# Striptease-Teensy4_1.net
KiCad netlist of a schematic drawn in EAGLE
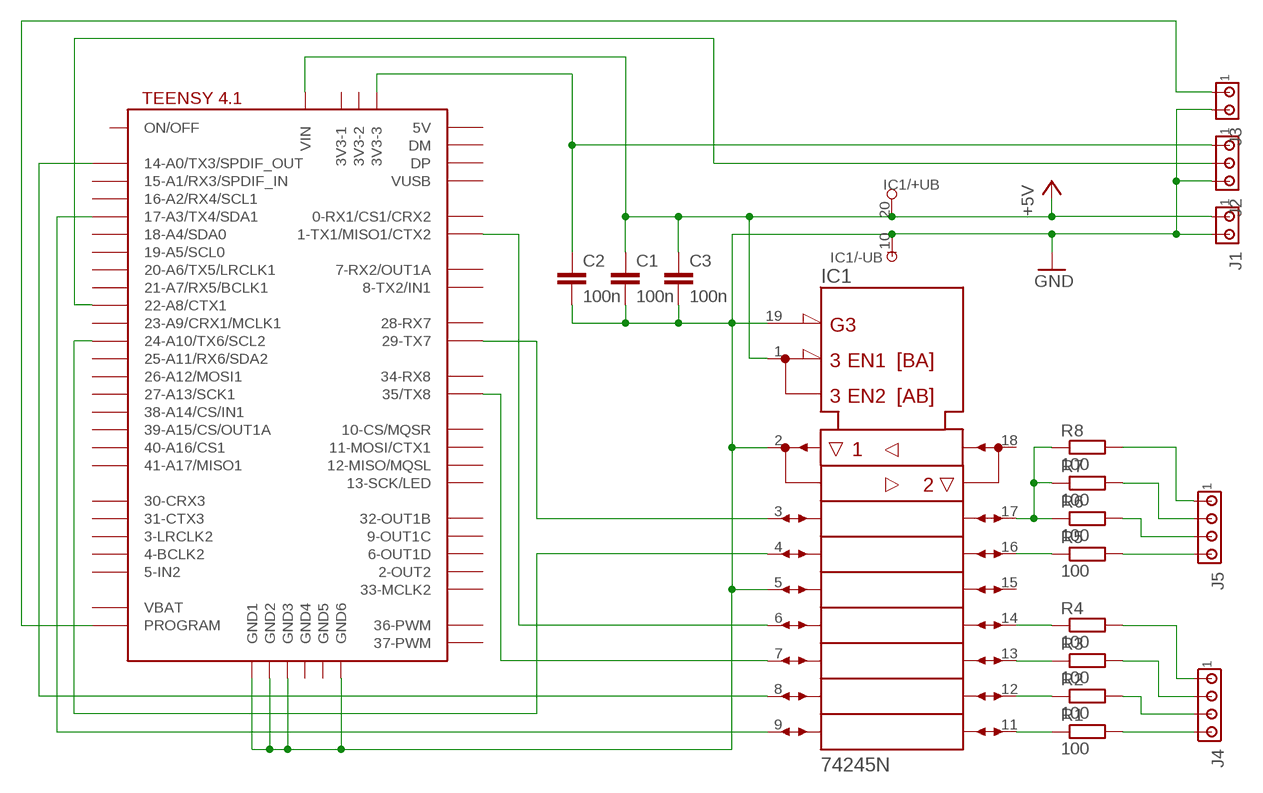
[diagram p0: schematic, sheet 1]

(export (version "E")
  (design (tool "Eeschema 10.0.6"))
  (components
    (comp (ref "C1")
      (value "100n")
      (footprint "eagle-import:C050-025X075")
      (libsource (lib "eagle-import") (part "C-EU050-025X075"))
    )
    (comp (ref "C2")
      (value "100n")
      (footprint "eagle-import:C050-025X075")
      (libsource (lib "eagle-import") (part "C-EU050-025X075"))
    )
    (comp (ref "C3")
      (value "100n")
      (footprint "eagle-import:C050-025X075")
      (libsource (lib "eagle-import") (part "C-EU050-025X075"))
    )
    (comp (ref "IC1")
      (value "74245N")
      (footprint "eagle-import:DIL20")
      (libsource (lib "eagle-import") (part "74245N"))
    )
    (comp (ref "J1")
      (value "MTA02-100")
      (footprint "eagle-import:10X02MTA")
      (libsource (lib "eagle-import") (part "MTA02-100"))
    )
    (comp (ref "J2")
      (value "MTA03-100")
      (footprint "eagle-import:10X03MTA")
      (libsource (lib "eagle-import") (part "MTA03-100"))
    )
    (comp (ref "J3")
      (value "MTA02-100")
      (footprint "eagle-import:10X02MTA")
      (libsource (lib "eagle-import") (part "MTA02-100"))
    )
    (comp (ref "J4")
      (value "MTA04-100")
      (footprint "eagle-import:10X04MTA")
      (libsource (lib "eagle-import") (part "MTA04-100"))
    )
    (comp (ref "J5")
      (value "MTA04-100")
      (footprint "eagle-import:10X04MTA")
      (libsource (lib "eagle-import") (part "MTA04-100"))
    )
    (comp (ref "R1")
      (value "100")
      (footprint "eagle-import:0207_10")
      (libsource (lib "eagle-import") (part "R-EU_0207/10"))
    )
    (comp (ref "R2")
      (value "100")
      (footprint "eagle-import:0207_10")
      (libsource (lib "eagle-import") (part "R-EU_0207/10"))
    )
    (comp (ref "R3")
      (value "100")
      (footprint "eagle-import:0207_10")
      (libsource (lib "eagle-import") (part "R-EU_0207/10"))
    )
    (comp (ref "R4")
      (value "100")
      (footprint "eagle-import:0207_10")
      (libsource (lib "eagle-import") (part "R-EU_0207/10"))
    )
    (comp (ref "R5")
      (value "100")
      (footprint "eagle-import:0207_10")
      (libsource (lib "eagle-import") (part "R-EU_0207/10"))
    )
    (comp (ref "R6")
      (value "100")
      (footprint "eagle-import:0207_10")
      (libsource (lib "eagle-import") (part "R-EU_0207/10"))
    )
    (comp (ref "R7")
      (value "100")
      (footprint "eagle-import:0207_10")
      (libsource (lib "eagle-import") (part "R-EU_0207/10"))
    )
    (comp (ref "R8")
      (value "100")
      (footprint "eagle-import:0207_10")
      (libsource (lib "eagle-import") (part "R-EU_0207/10"))
    )
    (comp (ref "U$3")
      (value "TEENSY41-E")
      (footprint "eagle-import:TENNSY41-E")
      (libsource (lib "eagle-import") (part "TEENSY41-E"))
    )
  )
  (nets
    (net (code "1") (name "+5V") (class "Default")
      (node (ref "C1") (pin "1") (pinfunction "1_1") (pintype "passive"))
      (node (ref "C3") (pin "1") (pinfunction "1_1") (pintype "passive"))
      (node (ref "IC1") (pin "1") (pinfunction "DIR_1") (pintype "input"))
      (node (ref "IC1") (pin "20") (pinfunction "+UB_20") (pintype "power_in"))
      (node (ref "J1") (pin "1") (pinfunction "1_1") (pintype "passive"))
      (node (ref "U$3") (pin "VIN") (pinfunction "VIN_VIN") (pintype "bidirectional"))
    )
    (net (code "2") (name "GND") (class "Default")
      (node (ref "C1") (pin "2") (pinfunction "2_2") (pintype "passive"))
      (node (ref "C2") (pin "2") (pinfunction "2_2") (pintype "passive"))
      (node (ref "C3") (pin "2") (pinfunction "2_2") (pintype "passive"))
      (node (ref "IC1") (pin "10") (pinfunction "-UB_10") (pintype "power_in"))
      (node (ref "IC1") (pin "19") (pinfunction "~{G}_19") (pintype "input"))
      (node (ref "IC1") (pin "2") (pinfunction "A1_2") (pintype "bidirectional"))
      (node (ref "IC1") (pin "5") (pinfunction "A4_5") (pintype "bidirectional"))
      (node (ref "J1") (pin "2") (pinfunction "2_2") (pintype "passive"))
      (node (ref "J2") (pin "3") (pinfunction "3_3") (pintype "passive"))
      (node (ref "J3") (pin "2") (pinfunction "2_2") (pintype "passive"))
      (node (ref "U$3") (pin "GND1") (pinfunction "GND1_GND1") (pintype "bidirectional"))
      (node (ref "U$3") (pin "GND2") (pinfunction "GND2_GND2") (pintype "bidirectional"))
      (node (ref "U$3") (pin "GND3") (pinfunction "GND3_GND3") (pintype "bidirectional"))
      (node (ref "U$3") (pin "GND6") (pinfunction "GND6_GND6") (pintype "bidirectional"))
    )
    (net (code "3") (name "Net-(C2-Pad1)") (class "Default")
      (node (ref "C2") (pin "1") (pinfunction "1_1") (pintype "passive"))
      (node (ref "J2") (pin "1") (pinfunction "1_1") (pintype "passive"))
      (node (ref "U$3") (pin "3V3-3") (pinfunction "3V3-3_3V3-3") (pintype "bidirectional"))
    )
    (net (code "4") (name "Net-(IC1C-A2)") (class "Default")
      (node (ref "IC1") (pin "3") (pinfunction "A2_3") (pintype "bidirectional"))
      (node (ref "U$3") (pin "29-TX7") (pinfunction "29-TX7_29-TX7") (pintype "bidirectional"))
    )
    (net (code "5") (name "Net-(IC1C-A3)") (class "Default")
      (node (ref "IC1") (pin "4") (pinfunction "A3_4") (pintype "bidirectional"))
      (node (ref "U$3") (pin "24-A10/TX6/SCL2") (pinfunction "24-A10/TX6/SCL2_24-A10/TX6/SCL2") (pintype "bidirectional"))
    )
    (net (code "6") (name "Net-(IC1C-A5)") (class "Default")
      (node (ref "IC1") (pin "6") (pinfunction "A5_6") (pintype "bidirectional"))
      (node (ref "U$3") (pin "1-TX1/MISO1/CTX2") (pinfunction "1-TX1/MISO1/CTX2_1-TX1/MISO1/CTX2") (pintype "bidirectional"))
    )
    (net (code "7") (name "Net-(IC1C-A6)") (class "Default")
      (node (ref "IC1") (pin "7") (pinfunction "A6_7") (pintype "bidirectional"))
      (node (ref "U$3") (pin "35-TX8") (pinfunction "35/TX8_35-TX8") (pintype "bidirectional"))
    )
    (net (code "8") (name "Net-(IC1C-A7)") (class "Default")
      (node (ref "IC1") (pin "8") (pinfunction "A7_8") (pintype "bidirectional"))
      (node (ref "U$3") (pin "14-A0/TX3/SPDIF_OUT") (pinfunction "14-A0/TX3/SPDIF_OUT_14-A0/TX3/SPDIF_OUT") (pintype "bidirectional"))
    )
    (net (code "9") (name "Net-(IC1C-A8)") (class "Default")
      (node (ref "IC1") (pin "9") (pinfunction "A8_9") (pintype "bidirectional"))
      (node (ref "U$3") (pin "17-A3/TX4/SDA1") (pinfunction "17-A3/TX4/SDA1_17-A3/TX4/SDA1") (pintype "bidirectional"))
    )
    (net (code "10") (name "Net-(IC1C-B2)") (class "Default")
      (node (ref "IC1") (pin "17") (pinfunction "B2_17") (pintype "bidirectional"))
      (node (ref "R6") (pin "1") (pinfunction "1_1") (pintype "passive"))
      (node (ref "R7") (pin "1") (pinfunction "1_1") (pintype "passive"))
      (node (ref "R8") (pin "1") (pinfunction "1_1") (pintype "passive"))
    )
    (net (code "11") (name "Net-(IC1C-B3)") (class "Default")
      (node (ref "IC1") (pin "16") (pinfunction "B3_16") (pintype "bidirectional"))
      (node (ref "R5") (pin "1") (pinfunction "1_1") (pintype "passive"))
    )
    (net (code "12") (name "Net-(IC1C-B5)") (class "Default")
      (node (ref "IC1") (pin "14") (pinfunction "B5_14") (pintype "bidirectional"))
      (node (ref "R4") (pin "1") (pinfunction "1_1") (pintype "passive"))
    )
    (net (code "13") (name "Net-(IC1C-B6)") (class "Default")
      (node (ref "IC1") (pin "13") (pinfunction "B6_13") (pintype "bidirectional"))
      (node (ref "R3") (pin "1") (pinfunction "1_1") (pintype "passive"))
    )
    (net (code "14") (name "Net-(IC1C-B7)") (class "Default")
      (node (ref "IC1") (pin "12") (pinfunction "B7_12") (pintype "bidirectional"))
      (node (ref "R2") (pin "1") (pinfunction "1_1") (pintype "passive"))
    )
    (net (code "15") (name "Net-(IC1C-B8)") (class "Default")
      (node (ref "IC1") (pin "11") (pinfunction "B8_11") (pintype "bidirectional"))
      (node (ref "R1") (pin "1") (pinfunction "1_1") (pintype "passive"))
    )
    (net (code "16") (name "Net-(J2-Pad2)") (class "Default")
      (node (ref "J2") (pin "2") (pinfunction "2_2") (pintype "passive"))
      (node (ref "U$3") (pin "22-A8/CTX1") (pinfunction "22-A8/CTX1_22-A8/CTX1") (pintype "bidirectional"))
    )
    (net (code "17") (name "Net-(J3-Pad1)") (class "Default")
      (node (ref "J3") (pin "1") (pinfunction "1_1") (pintype "passive"))
      (node (ref "U$3") (pin "PROGRAM") (pinfunction "PROGRAM_PROGRAM") (pintype "bidirectional"))
    )
    (net (code "18") (name "Net-(J4-Pad1)") (class "Default")
      (node (ref "J4") (pin "1") (pinfunction "1_1") (pintype "passive"))
      (node (ref "R4") (pin "2") (pinfunction "2_2") (pintype "passive"))
    )
    (net (code "19") (name "Net-(J4-Pad2)") (class "Default")
      (node (ref "J4") (pin "2") (pinfunction "2_2") (pintype "passive"))
      (node (ref "R3") (pin "2") (pinfunction "2_2") (pintype "passive"))
    )
    (net (code "20") (name "Net-(J4-Pad3)") (class "Default")
      (node (ref "J4") (pin "3") (pinfunction "3_3") (pintype "passive"))
      (node (ref "R2") (pin "2") (pinfunction "2_2") (pintype "passive"))
    )
    (net (code "21") (name "Net-(J4-Pad4)") (class "Default")
      (node (ref "J4") (pin "4") (pinfunction "4_4") (pintype "passive"))
      (node (ref "R1") (pin "2") (pinfunction "2_2") (pintype "passive"))
    )
    (net (code "22") (name "Net-(J5-Pad1)") (class "Default")
      (node (ref "J5") (pin "1") (pinfunction "1_1") (pintype "passive"))
      (node (ref "R8") (pin "2") (pinfunction "2_2") (pintype "passive"))
    )
    (net (code "23") (name "Net-(J5-Pad2)") (class "Default")
      (node (ref "J5") (pin "2") (pinfunction "2_2") (pintype "passive"))
      (node (ref "R7") (pin "2") (pinfunction "2_2") (pintype "passive"))
    )
    (net (code "24") (name "Net-(J5-Pad3)") (class "Default")
      (node (ref "J5") (pin "3") (pinfunction "3_3") (pintype "passive"))
      (node (ref "R6") (pin "2") (pinfunction "2_2") (pintype "passive"))
    )
    (net (code "25") (name "Net-(J5-Pad4)") (class "Default")
      (node (ref "J5") (pin "4") (pinfunction "4_4") (pintype "passive"))
      (node (ref "R5") (pin "2") (pinfunction "2_2") (pintype "passive"))
    )
    (net (code "26") (name "unconnected-(IC1C-B1-Pad18)") (class "Default")
      (node (ref "IC1") (pin "18") (pinfunction "B1_18") (pintype "bidirectional"))
    )
    (net (code "27") (name "unconnected-(IC1C-B4-Pad15)") (class "Default")
      (node (ref "IC1") (pin "15") (pinfunction "B4_15") (pintype "bidirectional"))
    )
    (net (code "28") (name "unconnected-(U$3-5V-Pad+5V)") (class "Default")
      (node (ref "U$3") (pin "+5V") (pinfunction "5V_+5V") (pintype "bidirectional"))
    )
    (net (code "29") (name "unconnected-(U$3-10-CS{slash}MQSR-Pad10-CS\\MQSR)") (class "Default")
      (node (ref "U$3") (pin "10-CS\\MQSR") (pinfunction "10-CS/MQSR_10-CS\\MQSR") (pintype "bidirectional"))
    )
    (net (code "30") (name "unconnected-(U$3-Pad0-RX1{slash}CS1{slash}CRX2)") (class "Default")
      (node (ref "U$3") (pin "0-RX1/CS1/CRX2") (pinfunction "0-RX1/CS1/CRX2_0-RX1/CS1/CRX2") (pintype "bidirectional"))
    )
    (net (code "31") (name "unconnected-(U$3-Pad2-OUT2)") (class "Default")
      (node (ref "U$3") (pin "2-OUT2") (pinfunction "2-OUT2_2-OUT2") (pintype "bidirectional"))
    )
    (net (code "32") (name "unconnected-(U$3-Pad3-LRCLK2)") (class "Default")
      (node (ref "U$3") (pin "3-LRCLK2") (pinfunction "3-LRCLK2_3-LRCLK2") (pintype "bidirectional"))
    )
    (net (code "33") (name "unconnected-(U$3-Pad3V3-1)") (class "Default")
      (node (ref "U$3") (pin "3V3-1") (pinfunction "3V3-1_3V3-1") (pintype "bidirectional"))
    )
    (net (code "34") (name "unconnected-(U$3-Pad3V3-2)") (class "Default")
      (node (ref "U$3") (pin "3V3-2") (pinfunction "3V3-2_3V3-2") (pintype "bidirectional"))
    )
    (net (code "35") (name "unconnected-(U$3-Pad4-BCLK2)") (class "Default")
      (node (ref "U$3") (pin "4-BCLK2") (pinfunction "4-BCLK2_4-BCLK2") (pintype "bidirectional"))
    )
    (net (code "36") (name "unconnected-(U$3-Pad5-IN2)") (class "Default")
      (node (ref "U$3") (pin "5-IN2") (pinfunction "5-IN2_5-IN2") (pintype "bidirectional"))
    )
    (net (code "37") (name "unconnected-(U$3-Pad6-OUT1D)") (class "Default")
      (node (ref "U$3") (pin "6-OUT1D") (pinfunction "6-OUT1D_6-OUT1D") (pintype "bidirectional"))
    )
    (net (code "38") (name "unconnected-(U$3-Pad7-RX2{slash}OUT1A)") (class "Default")
      (node (ref "U$3") (pin "7-RX2/OUT1A") (pinfunction "7-RX2/OUT1A_7-RX2/OUT1A") (pintype "bidirectional"))
    )
    (net (code "39") (name "unconnected-(U$3-Pad8-TX2{slash}IN1)") (class "Default")
      (node (ref "U$3") (pin "8-TX2/IN1") (pinfunction "8-TX2/IN1_8-TX2/IN1") (pintype "bidirectional"))
    )
    (net (code "40") (name "unconnected-(U$3-Pad9-OUT1C)") (class "Default")
      (node (ref "U$3") (pin "9-OUT1C") (pinfunction "9-OUT1C_9-OUT1C") (pintype "bidirectional"))
    )
    (net (code "41") (name "unconnected-(U$3-Pad11-MOSI{slash}CTX1)") (class "Default")
      (node (ref "U$3") (pin "11-MOSI/CTX1") (pinfunction "11-MOSI/CTX1_11-MOSI/CTX1") (pintype "bidirectional"))
    )
    (net (code "42") (name "unconnected-(U$3-Pad12-MISO{slash}MQSL)") (class "Default")
      (node (ref "U$3") (pin "12-MISO/MQSL") (pinfunction "12-MISO/MQSL_12-MISO/MQSL") (pintype "bidirectional"))
    )
    (net (code "43") (name "unconnected-(U$3-Pad13-SCK{slash}LED)") (class "Default")
      (node (ref "U$3") (pin "13-SCK/LED") (pinfunction "13-SCK/LED_13-SCK/LED") (pintype "bidirectional"))
    )
    (net (code "44") (name "unconnected-(U$3-Pad15-A1{slash}RX3{slash}SPDIF_IN)") (class "Default")
      (node (ref "U$3") (pin "15-A1/RX3/SPDIF_IN") (pinfunction "15-A1/RX3/SPDIF_IN_15-A1/RX3/SPDIF_IN") (pintype "bidirectional"))
    )
    (net (code "45") (name "unconnected-(U$3-Pad16-A2{slash}RX4{slash}SCL1)") (class "Default")
      (node (ref "U$3") (pin "16-A2/RX4/SCL1") (pinfunction "16-A2/RX4/SCL1_16-A2/RX4/SCL1") (pintype "bidirectional"))
    )
    (net (code "46") (name "unconnected-(U$3-Pad18-A4{slash}SDA0)") (class "Default")
      (node (ref "U$3") (pin "18-A4/SDA0") (pinfunction "18-A4/SDA0_18-A4/SDA0") (pintype "bidirectional"))
    )
    (net (code "47") (name "unconnected-(U$3-Pad19-A5{slash}SCL0)") (class "Default")
      (node (ref "U$3") (pin "19-A5/SCL0") (pinfunction "19-A5/SCL0_19-A5/SCL0") (pintype "bidirectional"))
    )
    (net (code "48") (name "unconnected-(U$3-Pad20-A6{slash}TX5{slash}LRCLK1)") (class "Default")
      (node (ref "U$3") (pin "20-A6/TX5/LRCLK1") (pinfunction "20-A6/TX5/LRCLK1_20-A6/TX5/LRCLK1") (pintype "bidirectional"))
    )
    (net (code "49") (name "unconnected-(U$3-Pad21-A7{slash}RX5{slash}BCLK1)") (class "Default")
      (node (ref "U$3") (pin "21-A7/RX5/BCLK1") (pinfunction "21-A7/RX5/BCLK1_21-A7/RX5/BCLK1") (pintype "bidirectional"))
    )
    (net (code "50") (name "unconnected-(U$3-Pad23-A9{slash}CRX1{slash}MCLK1)") (class "Default")
      (node (ref "U$3") (pin "23-A9/CRX1/MCLK1") (pinfunction "23-A9/CRX1/MCLK1_23-A9/CRX1/MCLK1") (pintype "bidirectional"))
    )
    (net (code "51") (name "unconnected-(U$3-Pad25-A11{slash}RX6{slash}SDA2)") (class "Default")
      (node (ref "U$3") (pin "25-A11/RX6/SDA2") (pinfunction "25-A11/RX6/SDA2_25-A11/RX6/SDA2") (pintype "bidirectional"))
    )
    (net (code "52") (name "unconnected-(U$3-Pad26-A12{slash}MOSI1)") (class "Default")
      (node (ref "U$3") (pin "26-A12/MOSI1") (pinfunction "26-A12/MOSI1_26-A12/MOSI1") (pintype "bidirectional"))
    )
    (net (code "53") (name "unconnected-(U$3-Pad27-A13{slash}SCK1)") (class "Default")
      (node (ref "U$3") (pin "27-A13/SCK1") (pinfunction "27-A13/SCK1_27-A13/SCK1") (pintype "bidirectional"))
    )
    (net (code "54") (name "unconnected-(U$3-Pad28-RX7)") (class "Default")
      (node (ref "U$3") (pin "28-RX7") (pinfunction "28-RX7_28-RX7") (pintype "bidirectional"))
    )
    (net (code "55") (name "unconnected-(U$3-Pad30-CRX3)") (class "Default")
      (node (ref "U$3") (pin "30-CRX3") (pinfunction "30-CRX3_30-CRX3") (pintype "bidirectional"))
    )
    (net (code "56") (name "unconnected-(U$3-Pad31-CTX3)") (class "Default")
      (node (ref "U$3") (pin "31-CTX3") (pinfunction "31-CTX3_31-CTX3") (pintype "bidirectional"))
    )
    (net (code "57") (name "unconnected-(U$3-Pad32-OUT1B)") (class "Default")
      (node (ref "U$3") (pin "32-OUT1B") (pinfunction "32-OUT1B_32-OUT1B") (pintype "bidirectional"))
    )
    (net (code "58") (name "unconnected-(U$3-Pad33-MCLK2)") (class "Default")
      (node (ref "U$3") (pin "33-MCLK2") (pinfunction "33-MCLK2_33-MCLK2") (pintype "bidirectional"))
    )
    (net (code "59") (name "unconnected-(U$3-Pad34-RX8)") (class "Default")
      (node (ref "U$3") (pin "34-RX8") (pinfunction "34-RX8_34-RX8") (pintype "bidirectional"))
    )
    (net (code "60") (name "unconnected-(U$3-Pad36-PWM)") (class "Default")
      (node (ref "U$3") (pin "36-PWM") (pinfunction "36-PWM_36-PWM") (pintype "bidirectional"))
    )
    (net (code "61") (name "unconnected-(U$3-Pad37-PWM)") (class "Default")
      (node (ref "U$3") (pin "37-PWM") (pinfunction "37-PWM_37-PWM") (pintype "bidirectional"))
    )
    (net (code "62") (name "unconnected-(U$3-Pad38-A14{slash}CS{slash}IN1)") (class "Default")
      (node (ref "U$3") (pin "38-A14/CS/IN1") (pinfunction "38-A14/CS/IN1_38-A14/CS/IN1") (pintype "bidirectional"))
    )
    (net (code "63") (name "unconnected-(U$3-Pad39-A15{slash}CS{slash}OUT1A)") (class "Default")
      (node (ref "U$3") (pin "39-A15/CS/OUT1A") (pinfunction "39-A15/CS/OUT1A_39-A15/CS/OUT1A") (pintype "bidirectional"))
    )
    (net (code "64") (name "unconnected-(U$3-Pad40-A16{slash}CS1)") (class "Default")
      (node (ref "U$3") (pin "40-A16/CS1") (pinfunction "40-A16/CS1_40-A16/CS1") (pintype "bidirectional"))
    )
    (net (code "65") (name "unconnected-(U$3-Pad41-A17{slash}MISO1)") (class "Default")
      (node (ref "U$3") (pin "41-A17/MISO1") (pinfunction "41-A17/MISO1_41-A17/MISO1") (pintype "bidirectional"))
    )
    (net (code "66") (name "unconnected-(U$3-PadDM)") (class "Default")
      (node (ref "U$3") (pin "DM") (pinfunction "DM_DM") (pintype "bidirectional"))
    )
    (net (code "67") (name "unconnected-(U$3-PadDP)") (class "Default")
      (node (ref "U$3") (pin "DP") (pinfunction "DP_DP") (pintype "bidirectional"))
    )
    (net (code "68") (name "unconnected-(U$3-PadGND4)") (class "Default")
      (node (ref "U$3") (pin "GND4") (pinfunction "GND4_GND4") (pintype "bidirectional"))
    )
    (net (code "69") (name "unconnected-(U$3-PadGND5)") (class "Default")
      (node (ref "U$3") (pin "GND5") (pinfunction "GND5_GND5") (pintype "bidirectional"))
    )
    (net (code "70") (name "unconnected-(U$3-PadON{slash}OFF)") (class "Default")
      (node (ref "U$3") (pin "ON/OFF") (pinfunction "ON/OFF_ON/OFF") (pintype "bidirectional"))
    )
    (net (code "71") (name "unconnected-(U$3-PadVBAT)") (class "Default")
      (node (ref "U$3") (pin "VBAT") (pinfunction "VBAT_VBAT") (pintype "bidirectional"))
    )
    (net (code "72") (name "unconnected-(U$3-PadVUSB)") (class "Default")
      (node (ref "U$3") (pin "VUSB") (pinfunction "VUSB_VUSB") (pintype "bidirectional"))
    )
  )
)
